# StellariSpiAlt.net
KiCad netlist of a schematic drawn in EAGLE
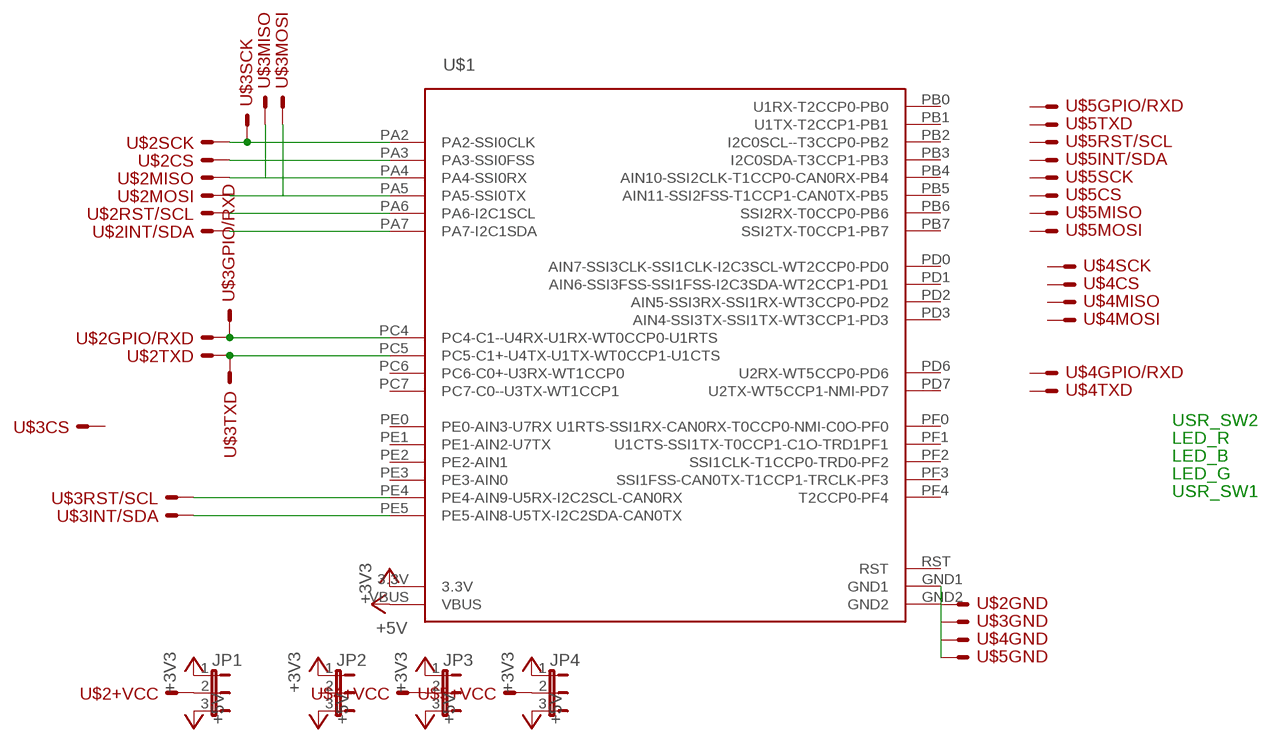
[diagram p0: schematic, sheet 1]

(export (version "E")
  (design (tool "Eeschema 10.0.6"))
  (components
    (comp (ref "JP1")
      (value "JP2E")
      (footprint "eagle-import:JP2")
      (libsource (lib "eagle-import") (part "JP2E"))
    )
    (comp (ref "JP2")
      (value "JP2E")
      (footprint "eagle-import:JP2")
      (libsource (lib "eagle-import") (part "JP2E"))
    )
    (comp (ref "JP3")
      (value "JP2E")
      (footprint "eagle-import:JP2")
      (libsource (lib "eagle-import") (part "JP2E"))
    )
    (comp (ref "JP4")
      (value "JP2E")
      (footprint "eagle-import:JP2")
      (libsource (lib "eagle-import") (part "JP2E"))
    )
    (comp (ref "U$1")
      (value "STELLARIS-LAUNCHPADSTELLARIS-LAUNCHPAD-XL")
      (footprint "eagle-import:LAUNCHPAD-XL")
      (libsource (lib "eagle-import") (part "STELLARIS-LAUNCHPADSTELLARIS-LAUNCHPAD-XL"))
    )
    (comp (ref "U$2")
      (value "SPI_BUS2")
      (footprint "eagle-import:SPI_BUS2")
      (libsource (lib "eagle-import") (part "SPI_BUS2"))
    )
    (comp (ref "U$3")
      (value "SPI_BUS2")
      (footprint "eagle-import:SPI_BUS2")
      (libsource (lib "eagle-import") (part "SPI_BUS2"))
    )
    (comp (ref "U$4")
      (value "SPI_BUS2")
      (footprint "eagle-import:SPI_BUS2")
      (libsource (lib "eagle-import") (part "SPI_BUS2"))
    )
    (comp (ref "U$5")
      (value "SPI_BUS2")
      (footprint "eagle-import:SPI_BUS2")
      (libsource (lib "eagle-import") (part "SPI_BUS2"))
    )
  )
  (nets
    (net (code "1") (name "+3V3") (class "Default")
      (node (ref "JP1") (pin "1") (pinfunction "1_1") (pintype "passive"))
      (node (ref "JP2") (pin "1") (pinfunction "1_1") (pintype "passive"))
      (node (ref "JP3") (pin "1") (pinfunction "1_1") (pintype "passive"))
      (node (ref "JP4") (pin "1") (pinfunction "1_1") (pintype "passive"))
      (node (ref "U$1") (pin "3.3V") (pinfunction "3.3V_3.3V") (pintype "power_in"))
    )
    (net (code "2") (name "+5V") (class "Default")
      (node (ref "JP1") (pin "3") (pinfunction "3_3") (pintype "passive"))
      (node (ref "JP2") (pin "3") (pinfunction "3_3") (pintype "passive"))
      (node (ref "JP3") (pin "3") (pinfunction "3_3") (pintype "passive"))
      (node (ref "JP4") (pin "3") (pinfunction "3_3") (pintype "passive"))
      (node (ref "U$1") (pin "VBUS") (pinfunction "VBUS_VBUS") (pintype "power_in"))
    )
    (net (code "3") (name "/RST") (class "Default")
      (node (ref "U$1") (pin "RST") (pinfunction "RST_RST") (pintype "power_in"))
    )
    (net (code "4") (name "Net-(U$1-PA2-SSI0CLK)") (class "Default")
      (node (ref "U$1") (pin "PA2") (pinfunction "PA2-SSI0CLK_PA2") (pintype "bidirectional"))
      (node (ref "U$2") (pin "SCK") (pinfunction "S_SCK") (pintype "passive"))
      (node (ref "U$3") (pin "SCK") (pinfunction "S_SCK") (pintype "passive"))
    )
    (net (code "5") (name "Net-(U$1-PA3-SSI0FSS)") (class "Default")
      (node (ref "U$1") (pin "PA3") (pinfunction "PA3-SSI0FSS_PA3") (pintype "bidirectional"))
      (node (ref "U$2") (pin "CS") (pinfunction "S_CS") (pintype "passive"))
    )
    (net (code "6") (name "Net-(U$1-PA4-SSI0RX)") (class "Default")
      (node (ref "U$1") (pin "PA4") (pinfunction "PA4-SSI0RX_PA4") (pintype "bidirectional"))
      (node (ref "U$2") (pin "MISO") (pinfunction "S_MISO") (pintype "passive"))
      (node (ref "U$3") (pin "MISO") (pinfunction "S_MISO") (pintype "passive"))
    )
    (net (code "7") (name "Net-(U$1-PA5-SSI0TX)") (class "Default")
      (node (ref "U$1") (pin "PA5") (pinfunction "PA5-SSI0TX_PA5") (pintype "bidirectional"))
      (node (ref "U$2") (pin "MOSI") (pinfunction "S_MOSI") (pintype "passive"))
      (node (ref "U$3") (pin "MOSI") (pinfunction "S_MOSI") (pintype "passive"))
    )
    (net (code "8") (name "Net-(U$1-PA6-I2C1SCL)") (class "Default")
      (node (ref "U$1") (pin "PA6") (pinfunction "PA6-I2C1SCL_PA6") (pintype "bidirectional"))
      (node (ref "U$2") (pin "RST/SCL") (pinfunction "S_RST/SCL") (pintype "passive"))
    )
    (net (code "9") (name "Net-(U$1-PA7-I2C1SDA)") (class "Default")
      (node (ref "U$1") (pin "PA7") (pinfunction "PA7-I2C1SDA_PA7") (pintype "bidirectional"))
      (node (ref "U$2") (pin "INT/SDA") (pinfunction "S_INT/SDA") (pintype "passive"))
    )
    (net (code "10") (name "Net-(U$1-PC4-C1--U4RX-U1RX-WT0CCP0-U1RTS)") (class "Default")
      (node (ref "U$1") (pin "PC4") (pinfunction "PC4-C1--U4RX-U1RX-WT0CCP0-U1RTS_PC4") (pintype "bidirectional"))
      (node (ref "U$2") (pin "GPIO/RXD") (pinfunction "S_GPIO/RXD") (pintype "passive"))
      (node (ref "U$3") (pin "GPIO/RXD") (pinfunction "S_GPIO/RXD") (pintype "passive"))
    )
    (net (code "11") (name "Net-(U$1-PC5-C1+-U4TX-U1TX-WT0CCP1-U1CTS)") (class "Default")
      (node (ref "U$1") (pin "PC5") (pinfunction "PC5-C1+-U4TX-U1TX-WT0CCP1-U1CTS_PC5") (pintype "bidirectional"))
      (node (ref "U$2") (pin "TXD") (pinfunction "S_TXD") (pintype "passive"))
      (node (ref "U$3") (pin "TXD") (pinfunction "S_TXD") (pintype "passive"))
    )
    (net (code "12") (name "Net-(U$1-PE4-AIN9-U5RX-I2C2SCL-CAN0RX)") (class "Default")
      (node (ref "U$1") (pin "PE4") (pinfunction "PE4-AIN9-U5RX-I2C2SCL-CAN0RX_PE4") (pintype "bidirectional"))
      (node (ref "U$3") (pin "RST/SCL") (pinfunction "S_RST/SCL") (pintype "passive"))
    )
    (net (code "13") (name "Net-(U$1-PE5-AIN8-U5TX-I2C2SDA-CAN0TX)") (class "Default")
      (node (ref "U$1") (pin "PE5") (pinfunction "PE5-AIN8-U5TX-I2C2SDA-CAN0TX_PE5") (pintype "bidirectional"))
      (node (ref "U$3") (pin "INT/SDA") (pinfunction "S_INT/SDA") (pintype "passive"))
    )
    (net (code "14") (name "Net-(U$2A-S)") (class "Default")
      (node (ref "JP1") (pin "2") (pinfunction "2_2") (pintype "passive"))
      (node (ref "U$2") (pin "+VCC") (pinfunction "S_+VCC") (pintype "passive"))
    )
    (net (code "15") (name "Net-(U$2C-S)") (class "Default")
      (node (ref "U$1") (pin "GND1") (pinfunction "GND1_GND1") (pintype "bidirectional"))
      (node (ref "U$1") (pin "GND2") (pinfunction "GND2_GND2") (pintype "power_in"))
      (node (ref "U$2") (pin "GND") (pinfunction "S_GND") (pintype "passive"))
      (node (ref "U$3") (pin "GND") (pinfunction "S_GND") (pintype "passive"))
      (node (ref "U$4") (pin "GND") (pinfunction "S_GND") (pintype "passive"))
      (node (ref "U$5") (pin "GND") (pinfunction "S_GND") (pintype "passive"))
    )
    (net (code "16") (name "Net-(U$4A-S)") (class "Default")
      (node (ref "JP3") (pin "2") (pinfunction "2_2") (pintype "passive"))
      (node (ref "U$4") (pin "+VCC") (pinfunction "S_+VCC") (pintype "passive"))
    )
    (net (code "17") (name "Net-(U$5A-S)") (class "Default")
      (node (ref "JP4") (pin "2") (pinfunction "2_2") (pintype "passive"))
      (node (ref "U$5") (pin "+VCC") (pinfunction "S_+VCC") (pintype "passive"))
    )
    (net (code "18") (name "unconnected-(JP2-Pad2)") (class "Default")
      (node (ref "JP2") (pin "2") (pinfunction "2_2") (pintype "passive"))
    )
    (net (code "19") (name "unconnected-(U$1-AIN4-SSI3TX-SSI1TX-WT3CCP1-PD3-PadPD3)") (class "Default")
      (node (ref "U$1") (pin "PD3") (pinfunction "AIN4-SSI3TX-SSI1TX-WT3CCP1-PD3_PD3") (pintype "bidirectional"))
    )
    (net (code "20") (name "unconnected-(U$1-AIN5-SSI3RX-SSI1RX-WT3CCP0-PD2-PadPD2)") (class "Default")
      (node (ref "U$1") (pin "PD2") (pinfunction "AIN5-SSI3RX-SSI1RX-WT3CCP0-PD2_PD2") (pintype "bidirectional"))
    )
    (net (code "21") (name "unconnected-(U$1-AIN6-SSI3FSS-SSI1FSS-I2C3SDA-WT2CCP1-PD1-PadPD1)") (class "Default")
      (node (ref "U$1") (pin "PD1") (pinfunction "AIN6-SSI3FSS-SSI1FSS-I2C3SDA-WT2CCP1-PD1_PD1") (pintype "bidirectional"))
    )
    (net (code "22") (name "unconnected-(U$1-AIN7-SSI3CLK-SSI1CLK-I2C3SCL-WT2CCP0-PD0-PadPD0)") (class "Default")
      (node (ref "U$1") (pin "PD0") (pinfunction "AIN7-SSI3CLK-SSI1CLK-I2C3SCL-WT2CCP0-PD0_PD0") (pintype "bidirectional"))
    )
    (net (code "23") (name "unconnected-(U$1-AIN10-SSI2CLK-T1CCP0-CAN0RX-PB4-PadPB4)") (class "Default")
      (node (ref "U$1") (pin "PB4") (pinfunction "AIN10-SSI2CLK-T1CCP0-CAN0RX-PB4_PB4") (pintype "bidirectional"))
    )
    (net (code "24") (name "unconnected-(U$1-AIN11-SSI2FSS-T1CCP1-CAN0TX-PB5-PadPB5)") (class "Default")
      (node (ref "U$1") (pin "PB5") (pinfunction "AIN11-SSI2FSS-T1CCP1-CAN0TX-PB5_PB5") (pintype "bidirectional"))
    )
    (net (code "25") (name "unconnected-(U$1-I2C0SCL--T3CCP0-PB2-PadPB2)") (class "Default")
      (node (ref "U$1") (pin "PB2") (pinfunction "I2C0SCL--T3CCP0-PB2_PB2") (pintype "bidirectional"))
    )
    (net (code "26") (name "unconnected-(U$1-I2C0SDA-T3CCP1-PB3-PadPB3)") (class "Default")
      (node (ref "U$1") (pin "PB3") (pinfunction "I2C0SDA-T3CCP1-PB3_PB3") (pintype "bidirectional"))
    )
    (net (code "27") (name "unconnected-(U$1-PC6-C0+-U3RX-WT1CCP0-PadPC6)") (class "Default")
      (node (ref "U$1") (pin "PC6") (pinfunction "PC6-C0+-U3RX-WT1CCP0_PC6") (pintype "bidirectional"))
    )
    (net (code "28") (name "unconnected-(U$1-PC7-C0--U3TX-WT1CCP1-PadPC7)") (class "Default")
      (node (ref "U$1") (pin "PC7") (pinfunction "PC7-C0--U3TX-WT1CCP1_PC7") (pintype "bidirectional"))
    )
    (net (code "29") (name "unconnected-(U$1-PE0-AIN3-U7RX-PadPE0)") (class "Default")
      (node (ref "U$1") (pin "PE0") (pinfunction "PE0-AIN3-U7RX_PE0") (pintype "bidirectional"))
    )
    (net (code "30") (name "unconnected-(U$1-PE1-AIN2-U7TX-PadPE1)") (class "Default")
      (node (ref "U$1") (pin "PE1") (pinfunction "PE1-AIN2-U7TX_PE1") (pintype "bidirectional"))
    )
    (net (code "31") (name "unconnected-(U$1-PE2-AIN1-PadPE2)") (class "Default")
      (node (ref "U$1") (pin "PE2") (pinfunction "PE2-AIN1_PE2") (pintype "bidirectional"))
    )
    (net (code "32") (name "unconnected-(U$1-PE3-AIN0-PadPE3)") (class "Default")
      (node (ref "U$1") (pin "PE3") (pinfunction "PE3-AIN0_PE3") (pintype "bidirectional"))
    )
    (net (code "33") (name "unconnected-(U$1-SSI1CLK-T1CCP0-TRD0-PF2-PadPF2)") (class "Default")
      (node (ref "U$1") (pin "PF2") (pinfunction "SSI1CLK-T1CCP0-TRD0-PF2_PF2") (pintype "bidirectional"))
    )
    (net (code "34") (name "unconnected-(U$1-SSI1FSS-CAN0TX-T1CCP1-TRCLK-PF3-PadPF3)") (class "Default")
      (node (ref "U$1") (pin "PF3") (pinfunction "SSI1FSS-CAN0TX-T1CCP1-TRCLK-PF3_PF3") (pintype "bidirectional"))
    )
    (net (code "35") (name "unconnected-(U$1-SSI2RX-T0CCP0-PB6-PadPB6)") (class "Default")
      (node (ref "U$1") (pin "PB6") (pinfunction "SSI2RX-T0CCP0-PB6_PB6") (pintype "bidirectional"))
    )
    (net (code "36") (name "unconnected-(U$1-SSI2TX-T0CCP1-PB7-PadPB7)") (class "Default")
      (node (ref "U$1") (pin "PB7") (pinfunction "SSI2TX-T0CCP1-PB7_PB7") (pintype "bidirectional"))
    )
    (net (code "37") (name "unconnected-(U$1-T2CCP0-PF4-PadPF4)") (class "Default")
      (node (ref "U$1") (pin "PF4") (pinfunction "T2CCP0-PF4_PF4") (pintype "bidirectional"))
    )
    (net (code "38") (name "unconnected-(U$1-U1CTS-SSI1TX-T0CCP1-C1O-TRD1PF1-PadPF1)") (class "Default")
      (node (ref "U$1") (pin "PF1") (pinfunction "U1CTS-SSI1TX-T0CCP1-C1O-TRD1PF1_PF1") (pintype "bidirectional"))
    )
    (net (code "39") (name "unconnected-(U$1-U1RTS-SSI1RX-CAN0RX-T0CCP0-NMI-C0O-PF0-PadPF0)") (class "Default")
      (node (ref "U$1") (pin "PF0") (pinfunction "U1RTS-SSI1RX-CAN0RX-T0CCP0-NMI-C0O-PF0_PF0") (pintype "bidirectional"))
    )
    (net (code "40") (name "unconnected-(U$1-U1RX-T2CCP0-PB0-PadPB0)") (class "Default")
      (node (ref "U$1") (pin "PB0") (pinfunction "U1RX-T2CCP0-PB0_PB0") (pintype "bidirectional"))
    )
    (net (code "41") (name "unconnected-(U$1-U1TX-T2CCP1-PB1-PadPB1)") (class "Default")
      (node (ref "U$1") (pin "PB1") (pinfunction "U1TX-T2CCP1-PB1_PB1") (pintype "bidirectional"))
    )
    (net (code "42") (name "unconnected-(U$1-U2RX-WT5CCP0-PD6-PadPD6)") (class "Default")
      (node (ref "U$1") (pin "PD6") (pinfunction "U2RX-WT5CCP0-PD6_PD6") (pintype "bidirectional"))
    )
    (net (code "43") (name "unconnected-(U$1-U2TX-WT5CCP1-NMI-PD7-PadPD7)") (class "Default")
      (node (ref "U$1") (pin "PD7") (pinfunction "U2TX-WT5CCP1-NMI-PD7_PD7") (pintype "bidirectional"))
    )
    (net (code "44") (name "unconnected-(U$3B-S-PadCS)") (class "Default")
      (node (ref "U$3") (pin "CS") (pinfunction "S_CS") (pintype "passive"))
    )
    (net (code "45") (name "unconnected-(U$4B-S-PadCS)") (class "Default")
      (node (ref "U$4") (pin "CS") (pinfunction "S_CS") (pintype "passive"))
    )
    (net (code "46") (name "unconnected-(U$4D-S-PadGPIO{slash}RXD)") (class "Default")
      (node (ref "U$4") (pin "GPIO/RXD") (pinfunction "S_GPIO/RXD") (pintype "passive"))
    )
    (net (code "47") (name "unconnected-(U$4F-S-PadMISO)") (class "Default")
      (node (ref "U$4") (pin "MISO") (pinfunction "S_MISO") (pintype "passive"))
    )
    (net (code "48") (name "unconnected-(U$4G-S-PadMOSI)") (class "Default")
      (node (ref "U$4") (pin "MOSI") (pinfunction "S_MOSI") (pintype "passive"))
    )
    (net (code "49") (name "unconnected-(U$4I-S-PadSCK)") (class "Default")
      (node (ref "U$4") (pin "SCK") (pinfunction "S_SCK") (pintype "passive"))
    )
    (net (code "50") (name "unconnected-(U$4J-S-PadTXD)") (class "Default")
      (node (ref "U$4") (pin "TXD") (pinfunction "S_TXD") (pintype "passive"))
    )
    (net (code "51") (name "unconnected-(U$5B-S-PadCS)") (class "Default")
      (node (ref "U$5") (pin "CS") (pinfunction "S_CS") (pintype "passive"))
    )
    (net (code "52") (name "unconnected-(U$5D-S-PadGPIO{slash}RXD)") (class "Default")
      (node (ref "U$5") (pin "GPIO/RXD") (pinfunction "S_GPIO/RXD") (pintype "passive"))
    )
    (net (code "53") (name "unconnected-(U$5E-S-PadINT{slash}SDA)") (class "Default")
      (node (ref "U$5") (pin "INT/SDA") (pinfunction "S_INT/SDA") (pintype "passive"))
    )
    (net (code "54") (name "unconnected-(U$5F-S-PadMISO)") (class "Default")
      (node (ref "U$5") (pin "MISO") (pinfunction "S_MISO") (pintype "passive"))
    )
    (net (code "55") (name "unconnected-(U$5G-S-PadMOSI)") (class "Default")
      (node (ref "U$5") (pin "MOSI") (pinfunction "S_MOSI") (pintype "passive"))
    )
    (net (code "56") (name "unconnected-(U$5H-S-PadRST{slash}SCL)") (class "Default")
      (node (ref "U$5") (pin "RST/SCL") (pinfunction "S_RST/SCL") (pintype "passive"))
    )
    (net (code "57") (name "unconnected-(U$5I-S-PadSCK)") (class "Default")
      (node (ref "U$5") (pin "SCK") (pinfunction "S_SCK") (pintype "passive"))
    )
    (net (code "58") (name "unconnected-(U$5J-S-PadTXD)") (class "Default")
      (node (ref "U$5") (pin "TXD") (pinfunction "S_TXD") (pintype "passive"))
    )
  )
)
